# mpp_bldc_GAN.net
KiCad netlist of a schematic drawn in EAGLE
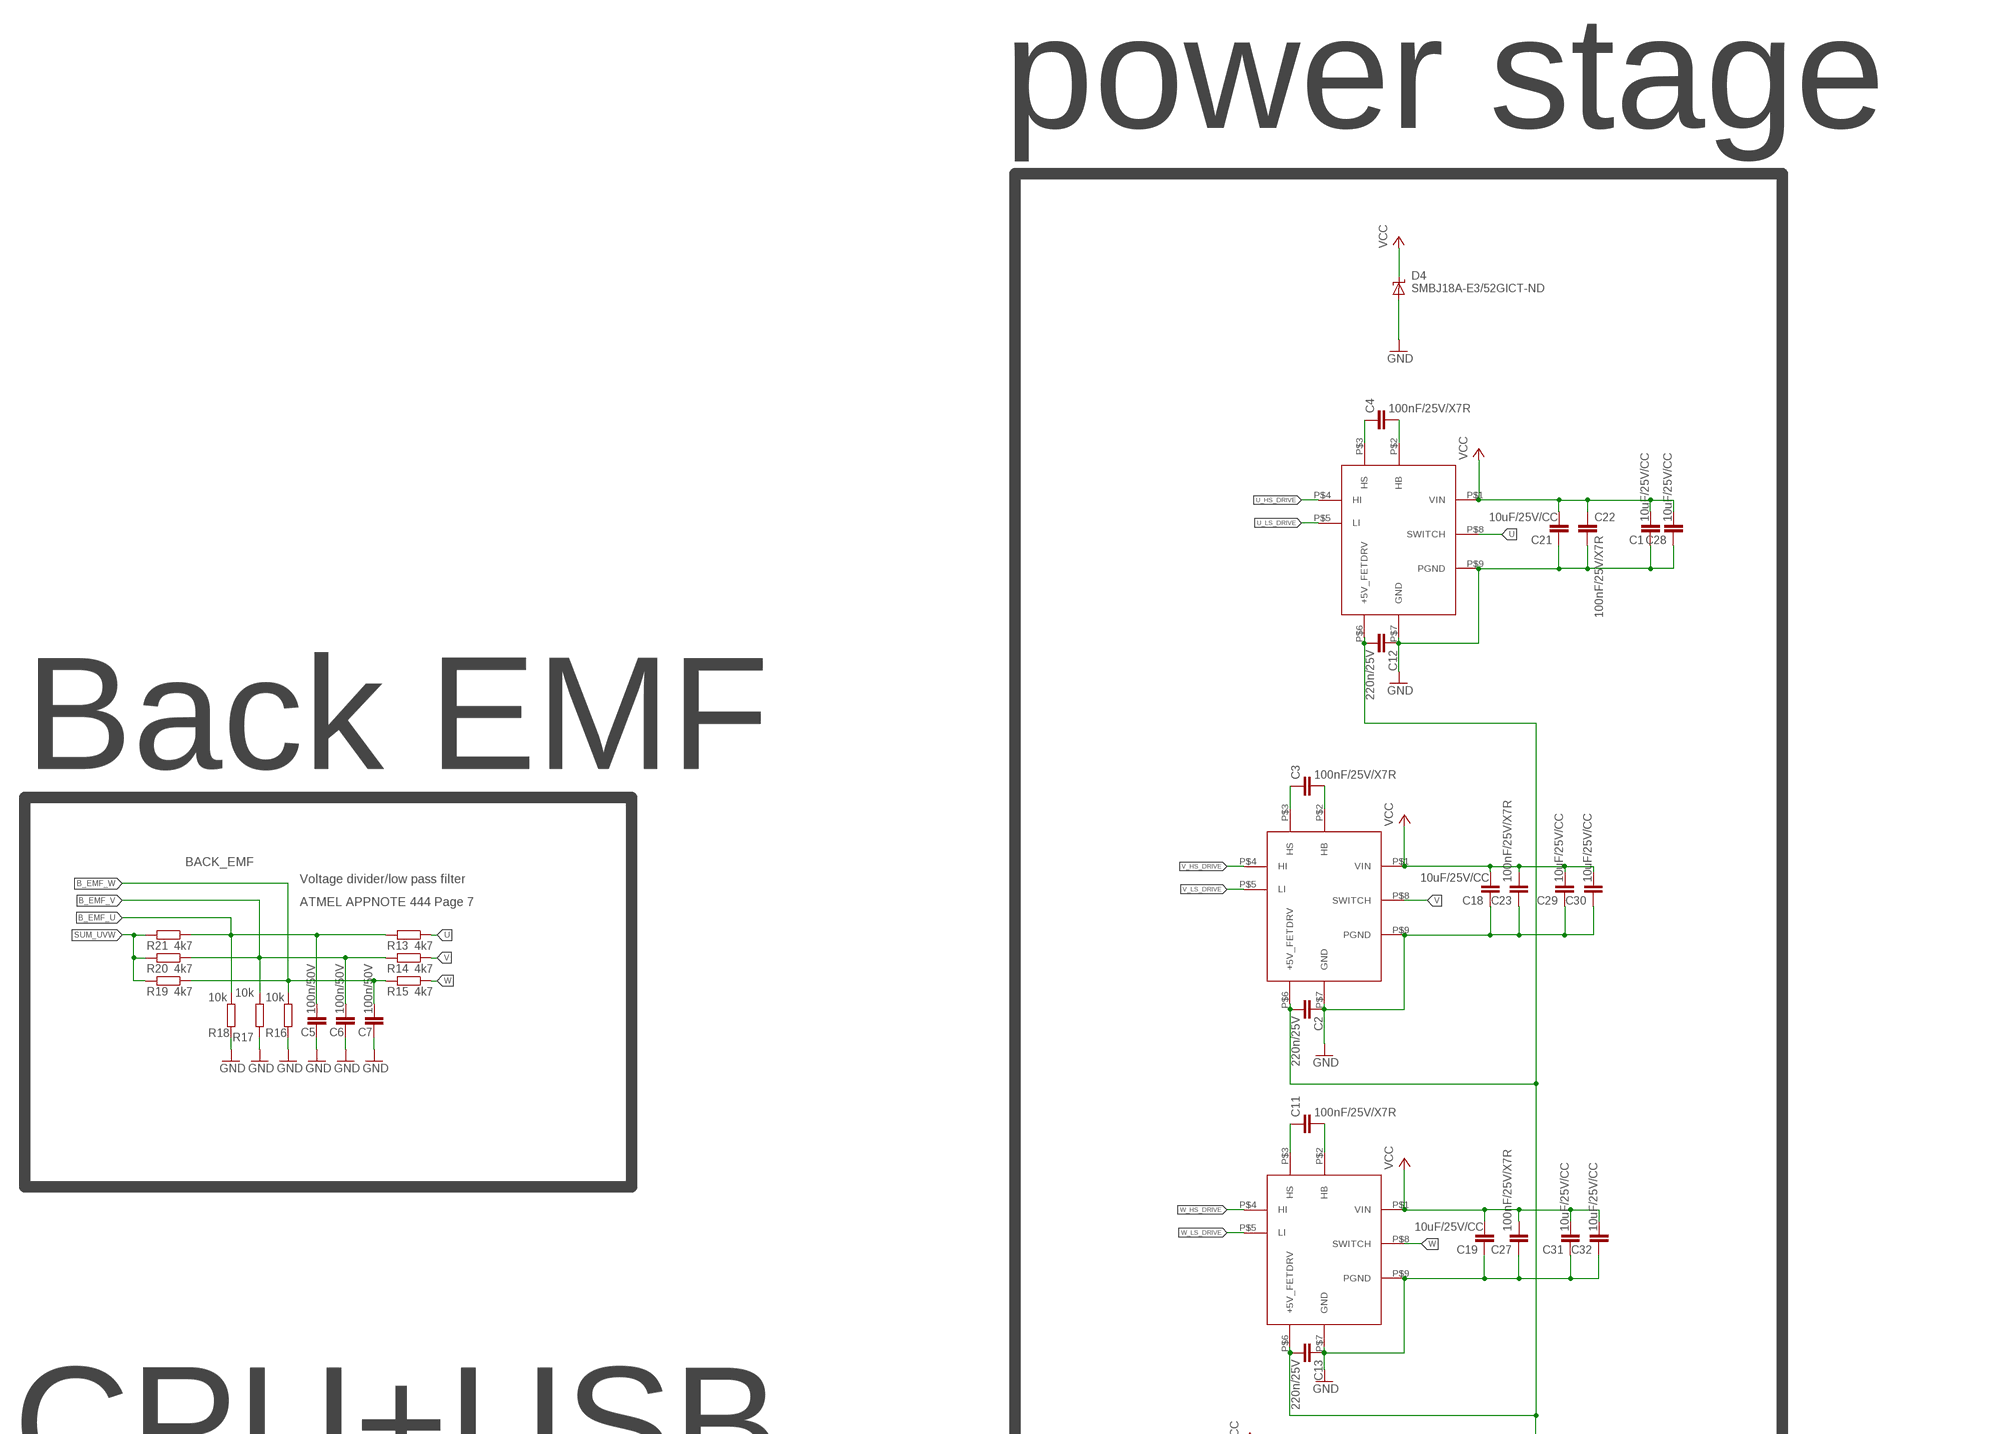
[diagram p0: schematic, sheet 1, part 1 of 2]
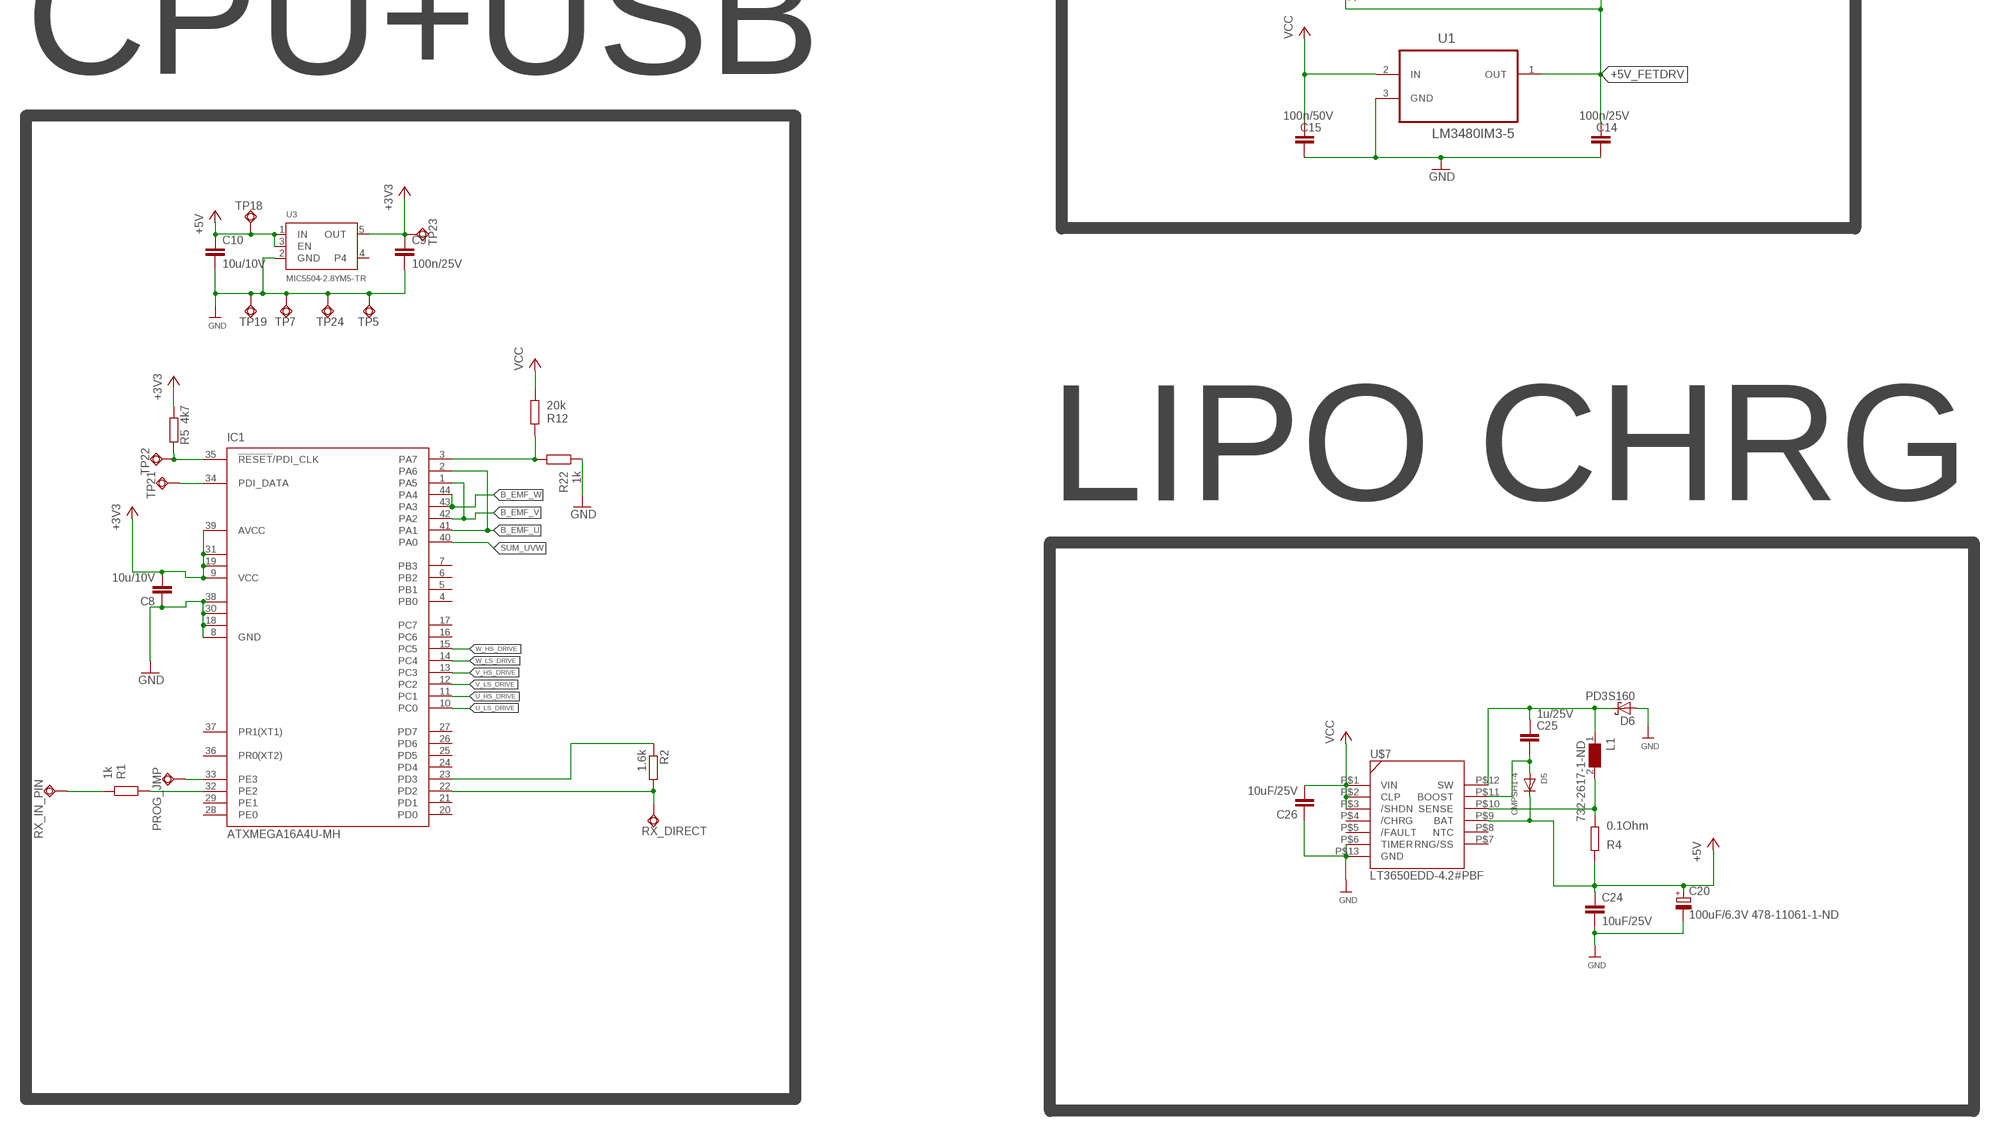
[diagram p1: schematic, sheet 1, part 2 of 2]

(export (version "E")
  (design (tool "Eeschema 10.0.6"))
  (components
    (comp (ref "C1")
      (value "10uF/25V/CC")
      (footprint "eagle-import:C1206")
      (libsource (lib "eagle-import") (part "rcl_334_C-EUC1206"))
    )
    (comp (ref "C2")
      (value "220n/25V")
      (footprint "eagle-import:C0402")
      (libsource (lib "eagle-import") (part "rcl_334_C-EUC0402"))
    )
    (comp (ref "C3")
      (value "100nF/25V/X7R")
      (footprint "eagle-import:C0402")
      (libsource (lib "eagle-import") (part "rcl_334_C-EUC0402"))
    )
    (comp (ref "C4")
      (value "100nF/25V/X7R")
      (footprint "eagle-import:C0402")
      (libsource (lib "eagle-import") (part "rcl_334_C-EUC0402"))
    )
    (comp (ref "C5")
      (value "100n/50V")
      (footprint "eagle-import:C0402")
      (libsource (lib "eagle-import") (part "C-EUC0402"))
    )
    (comp (ref "C6")
      (value "100n/50V")
      (footprint "eagle-import:C0402")
      (libsource (lib "eagle-import") (part "C-EUC0402"))
    )
    (comp (ref "C7")
      (value "100n/50V")
      (footprint "eagle-import:C0402")
      (libsource (lib "eagle-import") (part "C-EUC0402"))
    )
    (comp (ref "C8")
      (value "10u/10V")
      (footprint "eagle-import:C0603K")
      (libsource (lib "eagle-import") (part "C-EUC0603K"))
    )
    (comp (ref "C9")
      (value "100n/25V")
      (footprint "eagle-import:C0603")
      (libsource (lib "eagle-import") (part "C-EUC0603"))
    )
    (comp (ref "C10")
      (value "10u/10V")
      (footprint "eagle-import:C0603K")
      (libsource (lib "eagle-import") (part "C-EUC0603K"))
    )
    (comp (ref "C11")
      (value "100nF/25V/X7R")
      (footprint "eagle-import:C0402")
      (libsource (lib "eagle-import") (part "rcl_334_C-EUC0402"))
    )
    (comp (ref "C12")
      (value "220n/25V")
      (footprint "eagle-import:C0402")
      (libsource (lib "eagle-import") (part "rcl_334_C-EUC0402"))
    )
    (comp (ref "C13")
      (value "220n/25V")
      (footprint "eagle-import:C0402")
      (libsource (lib "eagle-import") (part "rcl_334_C-EUC0402"))
    )
    (comp (ref "C14")
      (value "100n/25V")
      (footprint "eagle-import:C0603")
      (libsource (lib "eagle-import") (part "C-EUC0603"))
    )
    (comp (ref "C15")
      (value "100n/50V")
      (footprint "eagle-import:C0603")
      (libsource (lib "eagle-import") (part "C-EUC0603"))
    )
    (comp (ref "C18")
      (value "10uF/25V/CC")
      (footprint "eagle-import:C1206")
      (libsource (lib "eagle-import") (part "rcl_334_C-EUC1206"))
    )
    (comp (ref "C19")
      (value "10uF/25V/CC")
      (footprint "eagle-import:C1206")
      (libsource (lib "eagle-import") (part "rcl_334_C-EUC1206"))
    )
    (comp (ref "C20")
      (value "100uF/6.3V 478-11061-1-ND")
      (footprint "eagle-import:CT7343")
      (libsource (lib "eagle-import") (part "CPOL-EUCT7343"))
    )
    (comp (ref "C21")
      (value "10uF/25V/CC")
      (footprint "eagle-import:C1206")
      (libsource (lib "eagle-import") (part "rcl_334_C-EUC1206"))
    )
    (comp (ref "C22")
      (value "100nF/25V/X7R")
      (footprint "eagle-import:C0402")
      (libsource (lib "eagle-import") (part "rcl_334_C-EUC0402"))
    )
    (comp (ref "C23")
      (value "100nF/25V/X7R")
      (footprint "eagle-import:C0402")
      (libsource (lib "eagle-import") (part "rcl_334_C-EUC0402"))
    )
    (comp (ref "C24")
      (value "10uF/25V")
      (footprint "eagle-import:C0805")
      (libsource (lib "eagle-import") (part "C-EUC0805"))
    )
    (comp (ref "C25")
      (value "1u/25V")
      (footprint "eagle-import:C0603")
      (libsource (lib "eagle-import") (part "C-EUC0603"))
    )
    (comp (ref "C26")
      (value "10uF/25V")
      (footprint "eagle-import:C0805")
      (libsource (lib "eagle-import") (part "C-EUC0805"))
    )
    (comp (ref "C27")
      (value "100nF/25V/X7R")
      (footprint "eagle-import:C0402")
      (libsource (lib "eagle-import") (part "rcl_334_C-EUC0402"))
    )
    (comp (ref "C28")
      (value "10uF/25V/CC")
      (footprint "eagle-import:C1206")
      (libsource (lib "eagle-import") (part "rcl_334_C-EUC1206"))
    )
    (comp (ref "C29")
      (value "10uF/25V/CC")
      (footprint "eagle-import:C1206")
      (libsource (lib "eagle-import") (part "rcl_334_C-EUC1206"))
    )
    (comp (ref "C30")
      (value "10uF/25V/CC")
      (footprint "eagle-import:C1206")
      (libsource (lib "eagle-import") (part "rcl_334_C-EUC1206"))
    )
    (comp (ref "C31")
      (value "10uF/25V/CC")
      (footprint "eagle-import:C1206")
      (libsource (lib "eagle-import") (part "rcl_334_C-EUC1206"))
    )
    (comp (ref "C32")
      (value "10uF/25V/CC")
      (footprint "eagle-import:C1206")
      (libsource (lib "eagle-import") (part "rcl_334_C-EUC1206"))
    )
    (comp (ref "D4")
      (value "SMBJ18A-E3/52GICT-ND")
      (footprint "eagle-import:SMBJ")
      (libsource (lib "eagle-import") (part "SUPPRESSOR-SMBJ"))
    )
    (comp (ref "D5")
      (value "CMPSH1-4")
      (footprint "eagle-import:SOT23-R")
      (libsource (lib "eagle-import") (part "DIODESOT23_REFLOW"))
    )
    (comp (ref "D6")
      (value "PD3S160")
      (footprint "eagle-import:POWERDI323")
      (libsource (lib "eagle-import") (part "PD3S160"))
    )
    (comp (ref "IC1")
      (value "ATXMEGA16A4U-MH")
      (footprint "eagle-import:MLF44-TH")
      (libsource (lib "eagle-import") (part "XMEGA16A4M1"))
    )
    (comp (ref "L1")
      (value "732-2617-1-ND")
      (footprint "eagle-import:WE-TPC_2828")
      (fields (field (name "MPN") "744025001"))
      (libsource (lib "eagle-import") (part "WE-TPC_2828-744025001"))
    )
    (comp (ref "PROG_JMP")
      (value "TPSQTP19SQ")
      (footprint "eagle-import:TP19SQ")
      (libsource (lib "eagle-import") (part "TPSQTP19SQ"))
    )
    (comp (ref "R1")
      (value "1k")
      (footprint "eagle-import:R0603")
      (libsource (lib "eagle-import") (part "R-EU_R0603"))
    )
    (comp (ref "R2")
      (value "1.6k")
      (footprint "eagle-import:R0402")
      (libsource (lib "eagle-import") (part "resistor_348_R-EU_R0402"))
    )
    (comp (ref "R4")
      (value "0.1Ohm")
      (footprint "eagle-import:R0402")
      (libsource (lib "eagle-import") (part "R-EU_R0402"))
    )
    (comp (ref "R5")
      (value "4k7")
      (footprint "eagle-import:R0603")
      (libsource (lib "eagle-import") (part "R-EU_R0603"))
    )
    (comp (ref "R12")
      (value "20k")
      (footprint "eagle-import:R0402")
      (libsource (lib "eagle-import") (part "R-EU_R0402"))
    )
    (comp (ref "R13")
      (value "4k7")
      (footprint "eagle-import:R0402")
      (libsource (lib "eagle-import") (part "R-EU_R0402"))
    )
    (comp (ref "R14")
      (value "4k7")
      (footprint "eagle-import:R0402")
      (libsource (lib "eagle-import") (part "R-EU_R0402"))
    )
    (comp (ref "R15")
      (value "4k7")
      (footprint "eagle-import:R0402")
      (libsource (lib "eagle-import") (part "R-EU_R0402"))
    )
    (comp (ref "R16")
      (value "10k")
      (footprint "eagle-import:R0402")
      (libsource (lib "eagle-import") (part "R-EU_R0402"))
    )
    (comp (ref "R17")
      (value "10k")
      (footprint "eagle-import:R0402")
      (libsource (lib "eagle-import") (part "R-EU_R0402"))
    )
    (comp (ref "R18")
      (value "10k")
      (footprint "eagle-import:R0402")
      (libsource (lib "eagle-import") (part "R-EU_R0402"))
    )
    (comp (ref "R19")
      (value "4k7")
      (footprint "eagle-import:R0402")
      (libsource (lib "eagle-import") (part "R-EU_R0402"))
    )
    (comp (ref "R20")
      (value "4k7")
      (footprint "eagle-import:R0402")
      (libsource (lib "eagle-import") (part "R-EU_R0402"))
    )
    (comp (ref "R21")
      (value "4k7")
      (footprint "eagle-import:R0402")
      (libsource (lib "eagle-import") (part "R-EU_R0402"))
    )
    (comp (ref "R22")
      (value "1k")
      (footprint "eagle-import:R0402")
      (libsource (lib "eagle-import") (part "R-EU_R0402"))
    )
    (comp (ref "RX_DIRECT")
      (value "TPSQTP11SQ")
      (footprint "eagle-import:TP11SQ")
      (libsource (lib "eagle-import") (part "TPSQTP11SQ"))
    )
    (comp (ref "RX_IN_PIN")
      (value "TPSQTP19SQ")
      (footprint "eagle-import:TP19SQ")
      (libsource (lib "eagle-import") (part "TPSQTP19SQ"))
    )
    (comp (ref "TP5")
      (value "TPSQTP19SQ")
      (footprint "eagle-import:TP19SQ")
      (libsource (lib "eagle-import") (part "TPSQTP19SQ"))
    )
    (comp (ref "TP7")
      (value "TPSQTP10R")
      (footprint "eagle-import:TP10R")
      (libsource (lib "eagle-import") (part "TPSQTP10R"))
    )
    (comp (ref "TP18")
      (value "TPSQTP19SQ")
      (footprint "eagle-import:TP19SQ")
      (libsource (lib "eagle-import") (part "TPSQTP19SQ"))
    )
    (comp (ref "TP19")
      (value "TPSQTP19SQ")
      (footprint "eagle-import:TP19SQ")
      (libsource (lib "eagle-import") (part "TPSQTP19SQ"))
    )
    (comp (ref "TP21")
      (value "TPSQTP15R")
      (footprint "eagle-import:TP15R")
      (libsource (lib "eagle-import") (part "TPSQTP15R"))
    )
    (comp (ref "TP22")
      (value "TPSQTP14SQ")
      (footprint "eagle-import:TP14SQ")
      (libsource (lib "eagle-import") (part "TPSQTP14SQ"))
    )
    (comp (ref "TP23")
      (value "TPSQTP14SQ")
      (footprint "eagle-import:TP14SQ")
      (libsource (lib "eagle-import") (part "TPSQTP14SQ"))
    )
    (comp (ref "TP24")
      (value "TPSQTP14SQ")
      (footprint "eagle-import:TP14SQ")
      (libsource (lib "eagle-import") (part "TPSQTP14SQ"))
    )
    (comp (ref "U$1")
      (value "LMG5200")
      (footprint "eagle-import:LMG5200")
      (libsource (lib "eagle-import") (part "LMG5200"))
    )
    (comp (ref "U$2")
      (value "LMG5200")
      (footprint "eagle-import:LMG5200")
      (libsource (lib "eagle-import") (part "LMG5200"))
    )
    (comp (ref "U$3")
      (value "LMG5200")
      (footprint "eagle-import:LMG5200")
      (libsource (lib "eagle-import") (part "LMG5200"))
    )
    (comp (ref "U$7")
      (value "LT3650EDD-4.2#PBF")
      (footprint "eagle-import:12-WFDFN")
      (libsource (lib "eagle-import") (part "LT3650-4.2"))
    )
    (comp (ref "U1")
      (value "LM3480IM3-5")
      (footprint "eagle-import:SOT95P251X112-3N")
      (fields (field (name "MPN") "LM3480IM3-12"))
      (libsource (lib "eagle-import") (part "LM3480IM3-12"))
    )
    (comp (ref "U3")
      (value "MIC5504-2.8YM5-TR")
      (footprint "eagle-import:SOT23-5")
      (libsource (lib "eagle-import") (part "VREG_SOT23-5"))
    )
  )
  (nets
    (net (code "1") (name "+3V3") (class "Default")
      (node (ref "C8") (pin "2") (pinfunction "2_2") (pintype "passive"))
      (node (ref "C9") (pin "1") (pinfunction "1_1") (pintype "passive"))
      (node (ref "IC1") (pin "19") (pinfunction "VCC1_19") (pintype "power_in"))
      (node (ref "IC1") (pin "31") (pinfunction "VCC2_31") (pintype "power_in"))
      (node (ref "IC1") (pin "39") (pinfunction "AVCC_39") (pintype "power_in"))
      (node (ref "IC1") (pin "9") (pinfunction "VCC_9") (pintype "power_in"))
      (node (ref "R5") (pin "1") (pinfunction "1_1") (pintype "passive"))
      (node (ref "TP23") (pin "TP") (pinfunction "TP_TP") (pintype "input"))
      (node (ref "U3") (pin "5") (pinfunction "OUT_5") (pintype "bidirectional"))
    )
    (net (code "2") (name "+5V") (class "Default")
      (node (ref "C10") (pin "1") (pinfunction "1_1") (pintype "passive"))
      (node (ref "C20") (pin "+") (pinfunction "+_+") (pintype "passive"))
      (node (ref "C24") (pin "1") (pinfunction "1_1") (pintype "passive"))
      (node (ref "D5") (pin "3") (pinfunction "C_3") (pintype "passive"))
      (node (ref "R4") (pin "2") (pinfunction "2_2") (pintype "passive"))
      (node (ref "TP18") (pin "TP") (pinfunction "TP_TP") (pintype "input"))
      (node (ref "U$7") (pin "P$9") (pinfunction "BAT_P$9") (pintype "bidirectional"))
      (node (ref "U3") (pin "1") (pinfunction "IN_1") (pintype "bidirectional"))
      (node (ref "U3") (pin "3") (pinfunction "EN_3") (pintype "bidirectional"))
    )
    (net (code "3") (name "+5V_FETDRV") (class "Default")
      (node (ref "C12") (pin "2") (pinfunction "2_2") (pintype "passive"))
      (node (ref "C13") (pin "2") (pinfunction "2_2") (pintype "passive"))
      (node (ref "C14") (pin "2") (pinfunction "2_2") (pintype "passive"))
      (node (ref "C2") (pin "2") (pinfunction "2_2") (pintype "passive"))
      (node (ref "U$1") (pin "P$6") (pinfunction "+5V_FETDRV_P$6") (pintype "power_in"))
      (node (ref "U$2") (pin "P$6") (pinfunction "+5V_FETDRV_P$6") (pintype "power_in"))
      (node (ref "U$3") (pin "P$6") (pinfunction "+5V_FETDRV_P$6") (pintype "power_in"))
      (node (ref "U1") (pin "1") (pinfunction "OUT_1") (pintype "output"))
    )
    (net (code "4") (name "B_EMF_U") (class "Default")
      (node (ref "C5") (pin "1") (pinfunction "1_1") (pintype "passive"))
      (node (ref "IC1") (pin "2") (pinfunction "PA6_2") (pintype "bidirectional"))
      (node (ref "IC1") (pin "41") (pinfunction "PA1_41") (pintype "bidirectional"))
      (node (ref "R13") (pin "2") (pinfunction "2_2") (pintype "passive"))
      (node (ref "R18") (pin "1") (pinfunction "1_1") (pintype "passive"))
      (node (ref "R21") (pin "1") (pinfunction "1_1") (pintype "passive"))
    )
    (net (code "5") (name "B_EMF_V") (class "Default")
      (node (ref "C6") (pin "1") (pinfunction "1_1") (pintype "passive"))
      (node (ref "IC1") (pin "1") (pinfunction "PA5_1") (pintype "bidirectional"))
      (node (ref "IC1") (pin "42") (pinfunction "PA2_42") (pintype "bidirectional"))
      (node (ref "R14") (pin "2") (pinfunction "2_2") (pintype "passive"))
      (node (ref "R17") (pin "1") (pinfunction "1_1") (pintype "passive"))
      (node (ref "R20") (pin "1") (pinfunction "1_1") (pintype "passive"))
    )
    (net (code "6") (name "B_EMF_W") (class "Default")
      (node (ref "C7") (pin "1") (pinfunction "1_1") (pintype "passive"))
      (node (ref "IC1") (pin "43") (pinfunction "PA3_43") (pintype "bidirectional"))
      (node (ref "IC1") (pin "44") (pinfunction "PA4_44") (pintype "bidirectional"))
      (node (ref "R15") (pin "2") (pinfunction "2_2") (pintype "passive"))
      (node (ref "R16") (pin "1") (pinfunction "1_1") (pintype "passive"))
      (node (ref "R19") (pin "1") (pinfunction "1_1") (pintype "passive"))
    )
    (net (code "7") (name "GND") (class "Default")
      (node (ref "C1") (pin "1") (pinfunction "1_1") (pintype "passive"))
      (node (ref "C10") (pin "2") (pinfunction "2_2") (pintype "passive"))
      (node (ref "C12") (pin "1") (pinfunction "1_1") (pintype "passive"))
      (node (ref "C13") (pin "1") (pinfunction "1_1") (pintype "passive"))
      (node (ref "C14") (pin "1") (pinfunction "1_1") (pintype "passive"))
      (node (ref "C15") (pin "1") (pinfunction "1_1") (pintype "passive"))
      (node (ref "C18") (pin "1") (pinfunction "1_1") (pintype "passive"))
      (node (ref "C19") (pin "1") (pinfunction "1_1") (pintype "passive"))
      (node (ref "C2") (pin "1") (pinfunction "1_1") (pintype "passive"))
      (node (ref "C20") (pin "-") (pinfunction "-_-") (pintype "passive"))
      (node (ref "C21") (pin "1") (pinfunction "1_1") (pintype "passive"))
      (node (ref "C22") (pin "2") (pinfunction "2_2") (pintype "passive"))
      (node (ref "C23") (pin "1") (pinfunction "1_1") (pintype "passive"))
      (node (ref "C24") (pin "2") (pinfunction "2_2") (pintype "passive"))
      (node (ref "C26") (pin "1") (pinfunction "1_1") (pintype "passive"))
      (node (ref "C27") (pin "1") (pinfunction "1_1") (pintype "passive"))
      (node (ref "C28") (pin "1") (pinfunction "1_1") (pintype "passive"))
      (node (ref "C29") (pin "1") (pinfunction "1_1") (pintype "passive"))
      (node (ref "C30") (pin "1") (pinfunction "1_1") (pintype "passive"))
      (node (ref "C31") (pin "1") (pinfunction "1_1") (pintype "passive"))
      (node (ref "C32") (pin "1") (pinfunction "1_1") (pintype "passive"))
      (node (ref "C5") (pin "2") (pinfunction "2_2") (pintype "passive"))
      (node (ref "C6") (pin "2") (pinfunction "2_2") (pintype "passive"))
      (node (ref "C7") (pin "2") (pinfunction "2_2") (pintype "passive"))
      (node (ref "C8") (pin "1") (pinfunction "1_1") (pintype "passive"))
      (node (ref "C9") (pin "2") (pinfunction "2_2") (pintype "passive"))
      (node (ref "D4") (pin "A") (pinfunction "A_A") (pintype "passive"))
      (node (ref "D6") (pin "A") (pinfunction "A_A") (pintype "passive"))
      (node (ref "IC1") (pin "18") (pinfunction "GND1_18") (pintype "power_in"))
      (node (ref "IC1") (pin "30") (pinfunction "GND2_30") (pintype "power_in"))
      (node (ref "IC1") (pin "38") (pinfunction "GND3_38") (pintype "power_in"))
      (node (ref "IC1") (pin "8") (pinfunction "GND_8") (pintype "power_in"))
      (node (ref "R16") (pin "2") (pinfunction "2_2") (pintype "passive"))
      (node (ref "R17") (pin "2") (pinfunction "2_2") (pintype "passive"))
      (node (ref "R18") (pin "2") (pinfunction "2_2") (pintype "passive"))
      (node (ref "R22") (pin "1") (pinfunction "1_1") (pintype "passive"))
      (node (ref "TP19") (pin "TP") (pinfunction "TP_TP") (pintype "input"))
      (node (ref "TP24") (pin "TP") (pinfunction "TP_TP") (pintype "input"))
      (node (ref "TP5") (pin "TP") (pinfunction "TP_TP") (pintype "input"))
      (node (ref "TP7") (pin "TP") (pinfunction "TP_TP") (pintype "input"))
      (node (ref "U$1") (pin "P$7") (pinfunction "GND_P$7") (pintype "power_in"))
      (node (ref "U$1") (pin "P$9") (pinfunction "PGND_P$9") (pintype "power_in"))
      (node (ref "U$2") (pin "P$7") (pinfunction "GND_P$7") (pintype "power_in"))
      (node (ref "U$2") (pin "P$9") (pinfunction "PGND_P$9") (pintype "power_in"))
      (node (ref "U$3") (pin "P$7") (pinfunction "GND_P$7") (pintype "power_in"))
      (node (ref "U$3") (pin "P$9") (pinfunction "PGND_P$9") (pintype "power_in"))
      (node (ref "U$7") (pin "P$13") (pinfunction "GND_P$13") (pintype "power_in"))
      (node (ref "U$7") (pin "P$6") (pinfunction "TIMER_P$6") (pintype "bidirectional"))
      (node (ref "U1") (pin "3") (pinfunction "GND_3") (pintype "passive"))
      (node (ref "U3") (pin "2") (pinfunction "GND_2") (pintype "bidirectional"))
    )
    (net (code "8") (name "Net-(D5-A)") (class "Default")
      (node (ref "C25") (pin "2") (pinfunction "2_2") (pintype "passive"))
      (node (ref "D5") (pin "1") (pinfunction "A_1") (pintype "passive"))
      (node (ref "U$7") (pin "P$11") (pinfunction "BOOST_P$11") (pintype "bidirectional"))
    )
    (net (code "9") (name "Net-(IC1-PA7)") (class "Default")
      (node (ref "IC1") (pin "3") (pinfunction "PA7_3") (pintype "bidirectional"))
      (node (ref "R12") (pin "2") (pinfunction "2_2") (pintype "passive"))
      (node (ref "R22") (pin "2") (pinfunction "2_2") (pintype "passive"))
    )
    (net (code "10") (name "Net-(IC1-PD2)") (class "Default")
      (node (ref "IC1") (pin "22") (pinfunction "PD2_22") (pintype "bidirectional"))
      (node (ref "R2") (pin "2") (pinfunction "2_2") (pintype "passive"))
      (node (ref "RX_DIRECT") (pin "TP") (pinfunction "TP_TP") (pintype "input"))
    )
    (net (code "11") (name "Net-(IC1-PD3)") (class "Default")
      (node (ref "IC1") (pin "23") (pinfunction "PD3_23") (pintype "bidirectional"))
      (node (ref "R2") (pin "1") (pinfunction "1_1") (pintype "passive"))
    )
    (net (code "12") (name "Net-(IC1-PDI_DATA)") (class "Default")
      (node (ref "IC1") (pin "34") (pinfunction "PDI_DATA_34") (pintype "bidirectional"))
      (node (ref "TP21") (pin "TP") (pinfunction "TP_TP") (pintype "input"))
    )
    (net (code "13") (name "Net-(IC1-PE2)") (class "Default")
      (node (ref "IC1") (pin "32") (pinfunction "PE2_32") (pintype "bidirectional"))
      (node (ref "R1") (pin "2") (pinfunction "2_2") (pintype "passive"))
    )
    (net (code "14") (name "Net-(IC1-PE3)") (class "Default")
      (node (ref "IC1") (pin "33") (pinfunction "PE3_33") (pintype "bidirectional"))
      (node (ref "PROG_JMP") (pin "TP") (pinfunction "TP_TP") (pintype "input"))
    )
    (net (code "15") (name "Net-(IC1-~{RESET}{slash}PDI_CLK)") (class "Default")
      (node (ref "IC1") (pin "35") (pinfunction "~{RESET}/PDI_CLK_35") (pintype "bidirectional"))
      (node (ref "R5") (pin "2") (pinfunction "2_2") (pintype "passive"))
      (node (ref "TP22") (pin "TP") (pinfunction "TP_TP") (pintype "input"))
    )
    (net (code "16") (name "Net-(R1-Pad1)") (class "Default")
      (node (ref "R1") (pin "1") (pinfunction "1_1") (pintype "passive"))
      (node (ref "RX_IN_PIN") (pin "TP") (pinfunction "TP_TP") (pintype "input"))
    )
    (net (code "17") (name "Net-(U$1-HB)") (class "Default")
      (node (ref "C11") (pin "2") (pinfunction "2_2") (pintype "passive"))
      (node (ref "U$1") (pin "P$2") (pinfunction "HB_P$2") (pintype "power_in"))
    )
    (net (code "18") (name "Net-(U$1-HS)") (class "Default")
      (node (ref "C11") (pin "1") (pinfunction "1_1") (pintype "passive"))
      (node (ref "U$1") (pin "P$3") (pinfunction "HS_P$3") (pintype "power_in"))
    )
    (net (code "19") (name "Net-(U$2-HB)") (class "Default")
      (node (ref "C3") (pin "2") (pinfunction "2_2") (pintype "passive"))
      (node (ref "U$2") (pin "P$2") (pinfunction "HB_P$2") (pintype "power_in"))
    )
    (net (code "20") (name "Net-(U$2-HS)") (class "Default")
      (node (ref "C3") (pin "1") (pinfunction "1_1") (pintype "passive"))
      (node (ref "U$2") (pin "P$3") (pinfunction "HS_P$3") (pintype "power_in"))
    )
    (net (code "21") (name "Net-(U$3-HB)") (class "Default")
      (node (ref "C4") (pin "2") (pinfunction "2_2") (pintype "passive"))
      (node (ref "U$3") (pin "P$2") (pinfunction "HB_P$2") (pintype "power_in"))
    )
    (net (code "22") (name "Net-(U$3-HS)") (class "Default")
      (node (ref "C4") (pin "1") (pinfunction "1_1") (pintype "passive"))
      (node (ref "U$3") (pin "P$3") (pinfunction "HS_P$3") (pintype "power_in"))
    )
    (net (code "23") (name "Net-(U$7-SENSE)") (class "Default")
      (node (ref "L1") (pin "2") (pinfunction "2_2") (pintype "passive"))
      (node (ref "R4") (pin "1") (pinfunction "1_1") (pintype "passive"))
      (node (ref "U$7") (pin "P$10") (pinfunction "SENSE_P$10") (pintype "bidirectional"))
    )
    (net (code "24") (name "Net-(U$7-SW)") (class "Default")
      (node (ref "C25") (pin "1") (pinfunction "1_1") (pintype "passive"))
      (node (ref "D6") (pin "C") (pinfunction "C_C") (pintype "passive"))
      (node (ref "L1") (pin "1") (pinfunction "1_1") (pintype "passive"))
      (node (ref "U$7") (pin "P$12") (pinfunction "SW_P$12") (pintype "bidirectional"))
    )
    (net (code "25") (name "SUM_UVW") (class "Default")
      (node (ref "IC1") (pin "40") (pinfunction "PA0_40") (pintype "bidirectional"))
      (node (ref "R19") (pin "2") (pinfunction "2_2") (pintype "passive"))
      (node (ref "R20") (pin "2") (pinfunction "2_2") (pintype "passive"))
      (node (ref "R21") (pin "2") (pinfunction "2_2") (pintype "passive"))
    )
    (net (code "26") (name "U") (class "Default")
      (node (ref "R13") (pin "1") (pinfunction "1_1") (pintype "passive"))
      (node (ref "U$3") (pin "P$8") (pinfunction "SWITCH_P$8") (pintype "power_in"))
    )
    (net (code "27") (name "U_HS_DRIVE") (class "Default")
      (node (ref "IC1") (pin "11") (pinfunction "PC1_11") (pintype "bidirectional"))
      (node (ref "U$3") (pin "P$4") (pinfunction "HI_P$4") (pintype "input"))
    )
    (net (code "28") (name "U_LS_DRIVE") (class "Default")
      (node (ref "IC1") (pin "10") (pinfunction "PC0_10") (pintype "bidirectional"))
      (node (ref "U$3") (pin "P$5") (pinfunction "LI_P$5") (pintype "input"))
    )
    (net (code "29") (name "V") (class "Default")
      (node (ref "R14") (pin "1") (pinfunction "1_1") (pintype "passive"))
      (node (ref "U$2") (pin "P$8") (pinfunction "SWITCH_P$8") (pintype "power_in"))
    )
    (net (code "30") (name "VCC") (class "Default")
      (node (ref "C1") (pin "2") (pinfunction "2_2") (pintype "passive"))
      (node (ref "C15") (pin "2") (pinfunction "2_2") (pintype "passive"))
      (node (ref "C18") (pin "2") (pinfunction "2_2") (pintype "passive"))
      (node (ref "C19") (pin "2") (pinfunction "2_2") (pintype "passive"))
      (node (ref "C21") (pin "2") (pinfunction "2_2") (pintype "passive"))
      (node (ref "C22") (pin "1") (pinfunction "1_1") (pintype "passive"))
      (node (ref "C23") (pin "2") (pinfunction "2_2") (pintype "passive"))
      (node (ref "C26") (pin "2") (pinfunction "2_2") (pintype "passive"))
      (node (ref "C27") (pin "2") (pinfunction "2_2") (pintype "passive"))
      (node (ref "C28") (pin "2") (pinfunction "2_2") (pintype "passive"))
      (node (ref "C29") (pin "2") (pinfunction "2_2") (pintype "passive"))
      (node (ref "C30") (pin "2") (pinfunction "2_2") (pintype "passive"))
      (node (ref "C31") (pin "2") (pinfunction "2_2") (pintype "passive"))
      (node (ref "C32") (pin "2") (pinfunction "2_2") (pintype "passive"))
      (node (ref "D4") (pin "C") (pinfunction "C_C") (pintype "passive"))
      (node (ref "R12") (pin "1") (pinfunction "1_1") (pintype "passive"))
      (node (ref "U$1") (pin "P$1") (pinfunction "VIN_P$1") (pintype "power_in"))
      (node (ref "U$2") (pin "P$1") (pinfunction "VIN_P$1") (pintype "power_in"))
      (node (ref "U$3") (pin "P$1") (pinfunction "VIN_P$1") (pintype "power_in"))
      (node (ref "U$7") (pin "P$1") (pinfunction "VIN_P$1") (pintype "power_in"))
      (node (ref "U$7") (pin "P$2") (pinfunction "CLP_P$2") (pintype "bidirectional"))
      (node (ref "U$7") (pin "P$3") (pinfunction "/SHDN_P$3") (pintype "bidirectional"))
      (node (ref "U1") (pin "2") (pinfunction "IN_2") (pintype "power_in"))
    )
    (net (code "31") (name "V_HS_DRIVE") (class "Default")
      (node (ref "IC1") (pin "13") (pinfunction "PC3_13") (pintype "bidirectional"))
      (node (ref "U$2") (pin "P$4") (pinfunction "HI_P$4") (pintype "input"))
    )
    (net (code "32") (name "V_LS_DRIVE") (class "Default")
      (node (ref "IC1") (pin "12") (pinfunction "PC2_12") (pintype "bidirectional"))
      (node (ref "U$2") (pin "P$5") (pinfunction "LI_P$5") (pintype "input"))
    )
    (net (code "33") (name "W") (class "Default")
      (node (ref "R15") (pin "1") (pinfunction "1_1") (pintype "passive"))
      (node (ref "U$1") (pin "P$8") (pinfunction "SWITCH_P$8") (pintype "power_in"))
    )
    (net (code "34") (name "W_HS_DRIVE") (class "Default")
      (node (ref "IC1") (pin "15") (pinfunction "PC5_15") (pintype "bidirectional"))
      (node (ref "U$1") (pin "P$4") (pinfunction "HI_P$4") (pintype "input"))
    )
    (net (code "35") (name "W_LS_DRIVE") (class "Default")
      (node (ref "IC1") (pin "14") (pinfunction "PC4_14") (pintype "bidirectional"))
      (node (ref "U$1") (pin "P$5") (pinfunction "LI_P$5") (pintype "input"))
    )
    (net (code "36") (name "unconnected-(IC1-PB0-Pad4)") (class "Default")
      (node (ref "IC1") (pin "4") (pinfunction "PB0_4") (pintype "bidirectional"))
    )
    (net (code "37") (name "unconnected-(IC1-PB1-Pad5)") (class "Default")
      (node (ref "IC1") (pin "5") (pinfunction "PB1_5") (pintype "bidirectional"))
    )
    (net (code "38") (name "unconnected-(IC1-PB2-Pad6)") (class "Default")
      (node (ref "IC1") (pin "6") (pinfunction "PB2_6") (pintype "bidirectional"))
    )
    (net (code "39") (name "unconnected-(IC1-PB3-Pad7)") (class "Default")
      (node (ref "IC1") (pin "7") (pinfunction "PB3_7") (pintype "bidirectional"))
    )
    (net (code "40") (name "unconnected-(IC1-PC6-Pad16)") (class "Default")
      (node (ref "IC1") (pin "16") (pinfunction "PC6_16") (pintype "bidirectional"))
    )
    (net (code "41") (name "unconnected-(IC1-PC7-Pad17)") (class "Default")
      (node (ref "IC1") (pin "17") (pinfunction "PC7_17") (pintype "bidirectional"))
    )
    (net (code "42") (name "unconnected-(IC1-PD0-Pad20)") (class "Default")
      (node (ref "IC1") (pin "20") (pinfunction "PD0_20") (pintype "bidirectional"))
    )
    (net (code "43") (name "unconnected-(IC1-PD1-Pad21)") (class "Default")
      (node (ref "IC1") (pin "21") (pinfunction "PD1_21") (pintype "bidirectional"))
    )
    (net (code "44") (name "unconnected-(IC1-PD4-Pad24)") (class "Default")
      (node (ref "IC1") (pin "24") (pinfunction "PD4_24") (pintype "bidirectional"))
    )
    (net (code "45") (name "unconnected-(IC1-PD5-Pad25)") (class "Default")
      (node (ref "IC1") (pin "25") (pinfunction "PD5_25") (pintype "bidirectional"))
    )
    (net (code "46") (name "unconnected-(IC1-PD6-Pad26)") (class "Default")
      (node (ref "IC1") (pin "26") (pinfunction "PD6_26") (pintype "bidirectional"))
    )
    (net (code "47") (name "unconnected-(IC1-PD7-Pad27)") (class "Default")
      (node (ref "IC1") (pin "27") (pinfunction "PD7_27") (pintype "bidirectional"))
    )
    (net (code "48") (name "unconnected-(IC1-PE0-Pad28)") (class "Default")
      (node (ref "IC1") (pin "28") (pinfunction "PE0_28") (pintype "bidirectional"))
    )
    (net (code "49") (name "unconnected-(IC1-PE1-Pad29)") (class "Default")
      (node (ref "IC1") (pin "29") (pinfunction "PE1_29") (pintype "bidirectional"))
    )
    (net (code "50") (name "unconnected-(IC1-PR0(XT2)-Pad36)") (class "Default")
      (node (ref "IC1") (pin "36") (pinfunction "PR0(XT2)_36") (pintype "bidirectional"))
    )
    (net (code "51") (name "unconnected-(IC1-PR1(XT1)-Pad37)") (class "Default")
      (node (ref "IC1") (pin "37") (pinfunction "PR1(XT1)_37") (pintype "bidirectional"))
    )
    (net (code "52") (name "unconnected-(U$7-NTC-PadP$8)") (class "Default")
      (node (ref "U$7") (pin "P$8") (pinfunction "NTC_P$8") (pintype "bidirectional"))
    )
    (net (code "53") (name "unconnected-(U$7-RNG{slash}SS-PadP$7)") (class "Default")
      (node (ref "U$7") (pin "P$7") (pinfunction "RNG/SS_P$7") (pintype "bidirectional"))
    )
    (net (code "54") (name "unconnected-(U$7-{slash}CHRG-PadP$4)") (class "Default")
      (node (ref "U$7") (pin "P$4") (pinfunction "/CHRG_P$4") (pintype "bidirectional"))
    )
    (net (code "55") (name "unconnected-(U$7-{slash}FAULT-PadP$5)") (class "Default")
      (node (ref "U$7") (pin "P$5") (pinfunction "/FAULT_P$5") (pintype "bidirectional"))
    )
    (net (code "56") (name "unconnected-(U3-P4-Pad4)") (class "Default")
      (node (ref "U3") (pin "4") (pinfunction "P4_4") (pintype "bidirectional"))
    )
  )
)
